# EKG_Modul_III.net
KiCad netlist of a schematic drawn in EAGLE
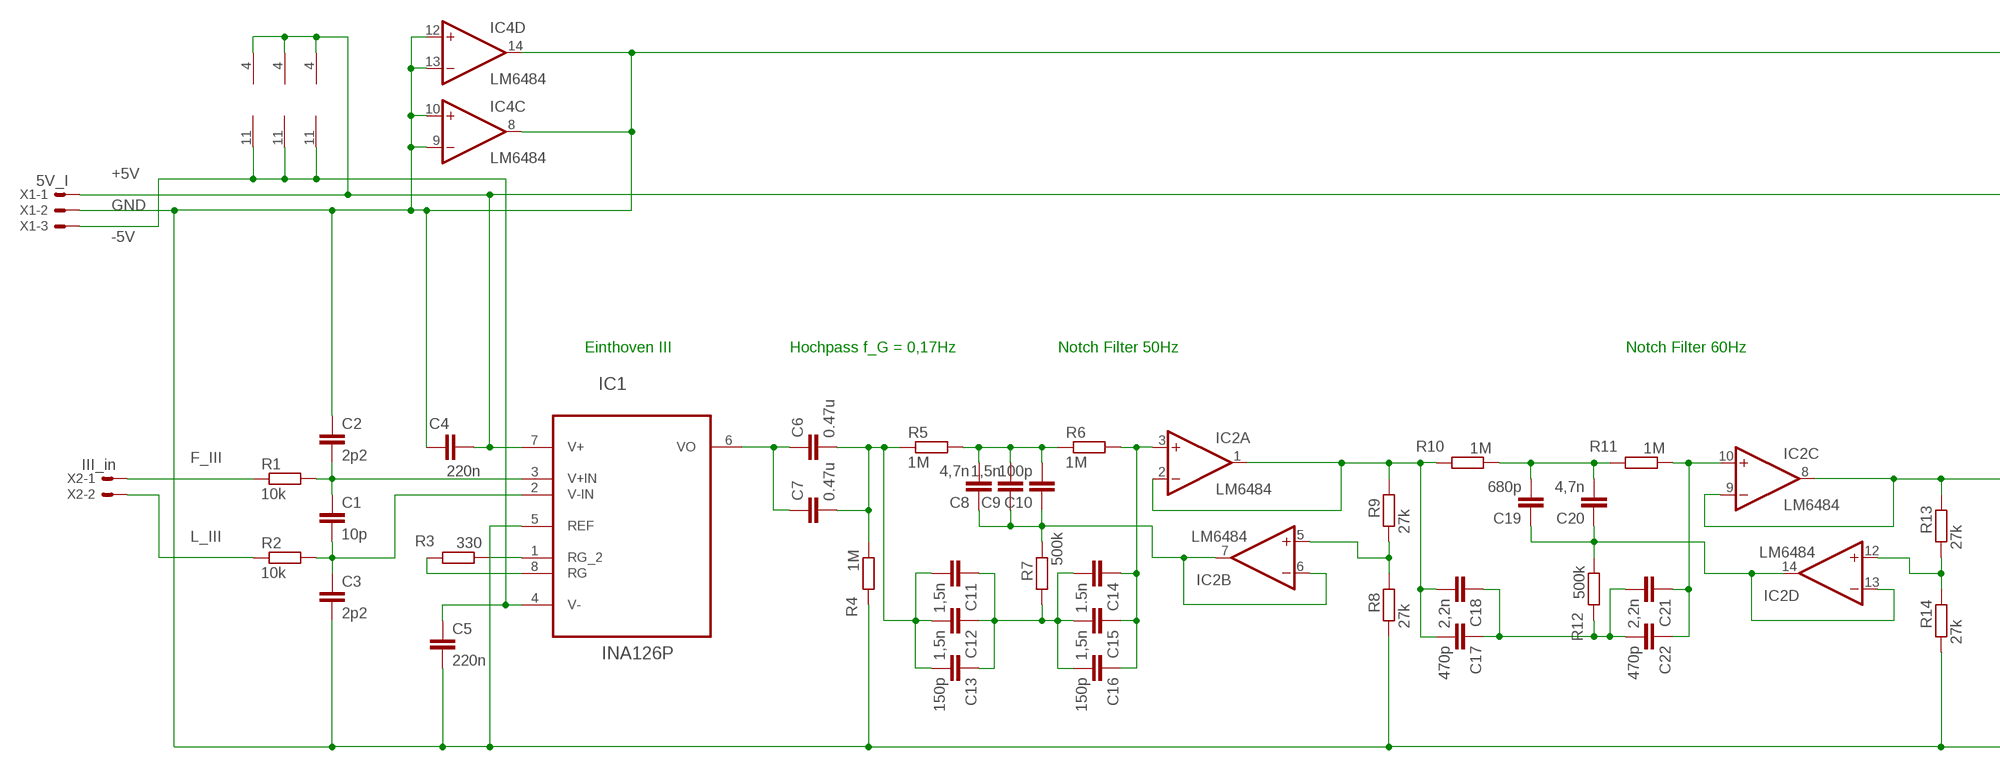
[diagram p0: schematic, sheet 1, part 1 of 2]
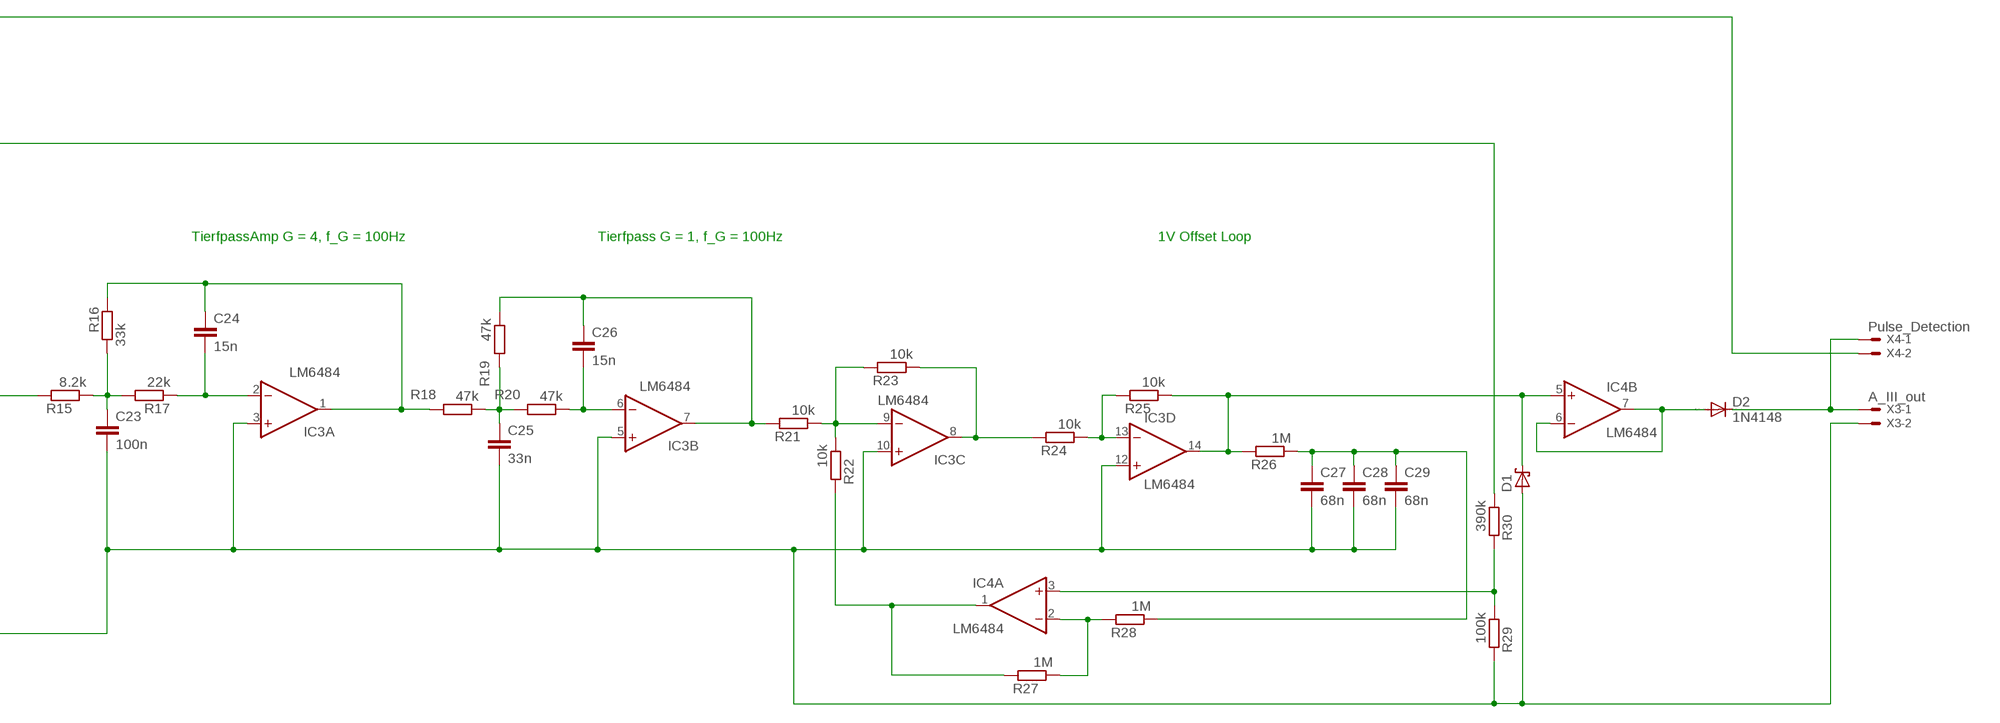
[diagram p1: schematic, sheet 1, part 2 of 2]

(export (version "E")
  (design (tool "Eeschema 10.0.6"))
  (components
    (comp (ref "C1")
      (value "10p")
      (footprint "eagle-import:C2.5-2")
      (libsource (lib "eagle-import") (part "C2.5/2"))
    )
    (comp (ref "C2")
      (value "2p2")
      (footprint "eagle-import:C2.5-2")
      (libsource (lib "eagle-import") (part "C2.5/2"))
    )
    (comp (ref "C3")
      (value "2p2")
      (footprint "eagle-import:C2.5-2")
      (libsource (lib "eagle-import") (part "C2.5/2"))
    )
    (comp (ref "C4")
      (value "220n")
      (footprint "eagle-import:C2.5-2")
      (libsource (lib "eagle-import") (part "C2.5/2"))
    )
    (comp (ref "C5")
      (value "220n")
      (footprint "eagle-import:C2.5-2")
      (libsource (lib "eagle-import") (part "C2.5/2"))
    )
    (comp (ref "C6")
      (value "0.47u")
      (footprint "eagle-import:C15B5")
      (libsource (lib "eagle-import") (part "C15/5"))
    )
    (comp (ref "C7")
      (value "0.47u")
      (footprint "eagle-import:C15B5")
      (libsource (lib "eagle-import") (part "C15/5"))
    )
    (comp (ref "C8")
      (value "4,7n")
      (footprint "eagle-import:C2.5-2")
      (libsource (lib "eagle-import") (part "C2.5/2"))
    )
    (comp (ref "C9")
      (value "1,5n")
      (footprint "eagle-import:C2.5-2")
      (libsource (lib "eagle-import") (part "C2.5/2"))
    )
    (comp (ref "C10")
      (value "100p")
      (footprint "eagle-import:C2.5-2")
      (libsource (lib "eagle-import") (part "C2.5/2"))
    )
    (comp (ref "C11")
      (value "1,5n")
      (footprint "eagle-import:C2.5-2")
      (libsource (lib "eagle-import") (part "C2.5/2"))
    )
    (comp (ref "C12")
      (value "1,5n")
      (footprint "eagle-import:C2.5-2")
      (libsource (lib "eagle-import") (part "C2.5/2"))
    )
    (comp (ref "C13")
      (value "150p")
      (footprint "eagle-import:C2.5-2")
      (libsource (lib "eagle-import") (part "C2.5/2"))
    )
    (comp (ref "C14")
      (value "1.5n")
      (footprint "eagle-import:C2.5-2")
      (libsource (lib "eagle-import") (part "C2.5/2"))
    )
    (comp (ref "C15")
      (value "1,5n")
      (footprint "eagle-import:C2.5-2")
      (libsource (lib "eagle-import") (part "C2.5/2"))
    )
    (comp (ref "C16")
      (value "150p")
      (footprint "eagle-import:C2.5-2")
      (libsource (lib "eagle-import") (part "C2.5/2"))
    )
    (comp (ref "C17")
      (value "470p")
      (footprint "eagle-import:C2.5-2")
      (libsource (lib "eagle-import") (part "C2.5/2"))
    )
    (comp (ref "C18")
      (value "2,2n")
      (footprint "eagle-import:C2.5-2")
      (libsource (lib "eagle-import") (part "C2.5/2"))
    )
    (comp (ref "C19")
      (value "680p")
      (footprint "eagle-import:C2.5-2")
      (libsource (lib "eagle-import") (part "C2.5/2"))
    )
    (comp (ref "C20")
      (value "4,7n")
      (footprint "eagle-import:C2.5-2")
      (libsource (lib "eagle-import") (part "C2.5/2"))
    )
    (comp (ref "C21")
      (value "2,2n")
      (footprint "eagle-import:C2.5-2")
      (libsource (lib "eagle-import") (part "C2.5/2"))
    )
    (comp (ref "C22")
      (value "470p")
      (footprint "eagle-import:C2.5-2")
      (libsource (lib "eagle-import") (part "C2.5/2"))
    )
    (comp (ref "C23")
      (value "100n")
      (footprint "eagle-import:C2.5-2")
      (libsource (lib "eagle-import") (part "C2.5/2"))
    )
    (comp (ref "C24")
      (value "15n")
      (footprint "eagle-import:C2.5-2")
      (libsource (lib "eagle-import") (part "C2.5/2"))
    )
    (comp (ref "C25")
      (value "33n")
      (footprint "eagle-import:C2.5-2")
      (libsource (lib "eagle-import") (part "C2.5/2"))
    )
    (comp (ref "C26")
      (value "15n")
      (footprint "eagle-import:C2.5-2")
      (libsource (lib "eagle-import") (part "C2.5/2"))
    )
    (comp (ref "C27")
      (value "68n")
      (footprint "eagle-import:C2.5-2")
      (libsource (lib "eagle-import") (part "C2.5/2"))
    )
    (comp (ref "C28")
      (value "68n")
      (footprint "eagle-import:C2.5-2")
      (libsource (lib "eagle-import") (part "C2.5/2"))
    )
    (comp (ref "C29")
      (value "68n")
      (footprint "eagle-import:C2.5-2")
      (libsource (lib "eagle-import") (part "C2.5/2"))
    )
    (comp (ref "D1")
      (value "SCHOTTKY-DIODEDO35-7")
      (footprint "eagle-import:DO35-7")
      (libsource (lib "eagle-import") (part "SCHOTTKY-DIODEDO35-7"))
    )
    (comp (ref "D2")
      (value "1N4148")
      (footprint "eagle-import:DO35-7")
      (libsource (lib "eagle-import") (part "1N4148DO35-7"))
    )
    (comp (ref "IC1")
      (value "INA126P")
      (footprint "eagle-import:DIP254P762X508-8")
      (fields (field (name "MF") "Texas Instruments"))
      (libsource (lib "eagle-import") (part "INA126P"))
    )
    (comp (ref "IC2")
      (value "LM6484")
      (footprint "eagle-import:DIL14")
      (libsource (lib "eagle-import") (part "QUAD_OPAMPP"))
    )
    (comp (ref "IC3")
      (value "LM6484")
      (footprint "eagle-import:DIL14")
      (libsource (lib "eagle-import") (part "QUAD_OPAMPP"))
    )
    (comp (ref "IC4")
      (value "LM6484")
      (footprint "eagle-import:DIL14")
      (libsource (lib "eagle-import") (part "QUAD_OPAMPP"))
    )
    (comp (ref "R1")
      (value "10k")
      (footprint "eagle-import:0207_7")
      (libsource (lib "eagle-import") (part "R-EU_0207/7"))
    )
    (comp (ref "R2")
      (value "10k")
      (footprint "eagle-import:0207_7")
      (libsource (lib "eagle-import") (part "R-EU_0207/7"))
    )
    (comp (ref "R3")
      (value "330")
      (footprint "eagle-import:0207_7")
      (libsource (lib "eagle-import") (part "R-EU_0207/7"))
    )
    (comp (ref "R4")
      (value "1M")
      (footprint "eagle-import:0207_7")
      (libsource (lib "eagle-import") (part "R-EU_0207/7"))
    )
    (comp (ref "R5")
      (value "1M")
      (footprint "eagle-import:0207_7")
      (libsource (lib "eagle-import") (part "R-EU_0207/7"))
    )
    (comp (ref "R6")
      (value "1M")
      (footprint "eagle-import:0207_7")
      (libsource (lib "eagle-import") (part "R-EU_0207/7"))
    )
    (comp (ref "R7")
      (value "500k")
      (footprint "eagle-import:0207_7")
      (libsource (lib "eagle-import") (part "R-EU_0207/7"))
    )
    (comp (ref "R8")
      (value "27k")
      (footprint "eagle-import:0207_7")
      (libsource (lib "eagle-import") (part "R-EU_0207/7"))
    )
    (comp (ref "R9")
      (value "27k")
      (footprint "eagle-import:0207_7")
      (libsource (lib "eagle-import") (part "R-EU_0207/7"))
    )
    (comp (ref "R10")
      (value "1M")
      (footprint "eagle-import:0207_7")
      (libsource (lib "eagle-import") (part "R-EU_0207/7"))
    )
    (comp (ref "R11")
      (value "1M")
      (footprint "eagle-import:0207_7")
      (libsource (lib "eagle-import") (part "R-EU_0207/7"))
    )
    (comp (ref "R12")
      (value "500k")
      (footprint "eagle-import:0207_7")
      (libsource (lib "eagle-import") (part "R-EU_0207/7"))
    )
    (comp (ref "R13")
      (value "27k")
      (footprint "eagle-import:0207_7")
      (libsource (lib "eagle-import") (part "R-EU_0207/7"))
    )
    (comp (ref "R14")
      (value "27k")
      (footprint "eagle-import:0207_7")
      (libsource (lib "eagle-import") (part "R-EU_0207/7"))
    )
    (comp (ref "R15")
      (value "8.2k")
      (footprint "eagle-import:0207_7")
      (libsource (lib "eagle-import") (part "R-EU_0207/7"))
    )
    (comp (ref "R16")
      (value "33k")
      (footprint "eagle-import:0207_7")
      (libsource (lib "eagle-import") (part "R-EU_0207/7"))
    )
    (comp (ref "R17")
      (value "22k")
      (footprint "eagle-import:0207_7")
      (libsource (lib "eagle-import") (part "R-EU_0207/7"))
    )
    (comp (ref "R18")
      (value "47k")
      (footprint "eagle-import:0207_7")
      (libsource (lib "eagle-import") (part "R-EU_0207/7"))
    )
    (comp (ref "R19")
      (value "47k")
      (footprint "eagle-import:0207_7")
      (libsource (lib "eagle-import") (part "R-EU_0207/7"))
    )
    (comp (ref "R20")
      (value "47k")
      (footprint "eagle-import:0207_7")
      (libsource (lib "eagle-import") (part "R-EU_0207/7"))
    )
    (comp (ref "R21")
      (value "10k")
      (footprint "eagle-import:0207_7")
      (libsource (lib "eagle-import") (part "R-EU_0207/7"))
    )
    (comp (ref "R22")
      (value "10k")
      (footprint "eagle-import:0207_7")
      (libsource (lib "eagle-import") (part "R-EU_0207/7"))
    )
    (comp (ref "R23")
      (value "10k")
      (footprint "eagle-import:0207_7")
      (libsource (lib "eagle-import") (part "R-EU_0207/7"))
    )
    (comp (ref "R24")
      (value "10k")
      (footprint "eagle-import:0207_7")
      (libsource (lib "eagle-import") (part "R-EU_0207/7"))
    )
    (comp (ref "R25")
      (value "10k")
      (footprint "eagle-import:0207_7")
      (libsource (lib "eagle-import") (part "R-EU_0207/7"))
    )
    (comp (ref "R26")
      (value "1M")
      (footprint "eagle-import:0207_7")
      (libsource (lib "eagle-import") (part "R-EU_0207/7"))
    )
    (comp (ref "R27")
      (value "1M")
      (footprint "eagle-import:0207_7")
      (libsource (lib "eagle-import") (part "R-EU_0207/7"))
    )
    (comp (ref "R28")
      (value "1M")
      (footprint "eagle-import:0207_7")
      (libsource (lib "eagle-import") (part "R-EU_0207/7"))
    )
    (comp (ref "R29")
      (value "100k")
      (footprint "eagle-import:0207_7")
      (libsource (lib "eagle-import") (part "R-EU_0207/7"))
    )
    (comp (ref "R30")
      (value "390k")
      (footprint "eagle-import:0207_7")
      (libsource (lib "eagle-import") (part "R-EU_0207/7"))
    )
    (comp (ref "X1")
      (value "5V_I")
      (footprint "eagle-import:JST-XH-03-PACKAGE-LONG-PAD")
      (libsource (lib "eagle-import") (part "JST-XH-03-PIN-LONG-PAD"))
    )
    (comp (ref "X2")
      (value "III_in")
      (footprint "eagle-import:JST-XH-02-PACKAGE-LONG-PAD")
      (libsource (lib "eagle-import") (part "JST-XH-02-PIN-LONG-PAD"))
    )
    (comp (ref "X3")
      (value "A_III_out")
      (footprint "eagle-import:JST-XH-02-PACKAGE-LONG-PAD")
      (libsource (lib "eagle-import") (part "JST-XH-02-PIN-LONG-PAD"))
    )
    (comp (ref "X4")
      (value "Pulse_Detection")
      (footprint "eagle-import:JST-XH-02-PACKAGE-LONG-PAD")
      (libsource (lib "eagle-import") (part "JST-XH-02-PIN-LONG-PAD"))
    )
  )
  (nets
    (net (code "1") (name "/+5V") (class "Default")
      (node (ref "C4") (pin "2") (pinfunction "2_2") (pintype "passive"))
      (node (ref "IC1") (pin "7") (pinfunction "V+_7") (pintype "power_in"))
      (node (ref "IC2") (pin "4") (pinfunction "V+_4") (pintype "power_in"))
      (node (ref "IC3") (pin "4") (pinfunction "V+_4") (pintype "power_in"))
      (node (ref "IC4") (pin "4") (pinfunction "V+_4") (pintype "power_in"))
      (node (ref "R30") (pin "1") (pinfunction "1_1") (pintype "passive"))
      (node (ref "X1") (pin "1") (pinfunction "S_1") (pintype "passive"))
    )
    (net (code "2") (name "/-5V") (class "Default")
      (node (ref "C5") (pin "1") (pinfunction "1_1") (pintype "passive"))
      (node (ref "IC1") (pin "4") (pinfunction "V-_4") (pintype "power_in"))
      (node (ref "IC2") (pin "11") (pinfunction "V-_11") (pintype "power_in"))
      (node (ref "IC3") (pin "11") (pinfunction "V-_11") (pintype "power_in"))
      (node (ref "IC4") (pin "11") (pinfunction "V-_11") (pintype "power_in"))
      (node (ref "X1") (pin "3") (pinfunction "S_3") (pintype "passive"))
    )
    (net (code "3") (name "/F_III") (class "Default")
      (node (ref "R1") (pin "1") (pinfunction "1_1") (pintype "passive"))
      (node (ref "X2") (pin "1") (pinfunction "S_1") (pintype "passive"))
    )
    (net (code "4") (name "/GND") (class "Default")
      (node (ref "C2") (pin "1") (pinfunction "1_1") (pintype "passive"))
      (node (ref "C23") (pin "2") (pinfunction "2_2") (pintype "passive"))
      (node (ref "C25") (pin "2") (pinfunction "2_2") (pintype "passive"))
      (node (ref "C27") (pin "2") (pinfunction "2_2") (pintype "passive"))
      (node (ref "C28") (pin "2") (pinfunction "2_2") (pintype "passive"))
      (node (ref "C29") (pin "2") (pinfunction "2_2") (pintype "passive"))
      (node (ref "C3") (pin "2") (pinfunction "2_2") (pintype "passive"))
      (node (ref "C4") (pin "1") (pinfunction "1_1") (pintype "passive"))
      (node (ref "C5") (pin "2") (pinfunction "2_2") (pintype "passive"))
      (node (ref "D1") (pin "A") (pinfunction "A_A") (pintype "passive"))
      (node (ref "IC1") (pin "5") (pinfunction "REF_5") (pintype "passive"))
      (node (ref "IC3") (pin "10") (pinfunction "+IN_10") (pintype "input"))
      (node (ref "IC3") (pin "12") (pinfunction "+IN_12") (pintype "input"))
      (node (ref "IC3") (pin "3") (pinfunction "+IN_3") (pintype "input"))
      (node (ref "IC3") (pin "5") (pinfunction "+IN_5") (pintype "input"))
      (node (ref "IC4") (pin "10") (pinfunction "+IN_10") (pintype "input"))
      (node (ref "IC4") (pin "12") (pinfunction "+IN_12") (pintype "input"))
      (node (ref "IC4") (pin "13") (pinfunction "-IN_13") (pintype "input"))
      (node (ref "IC4") (pin "14") (pinfunction "OUT_14") (pintype "output"))
      (node (ref "IC4") (pin "8") (pinfunction "OUT_8") (pintype "output"))
      (node (ref "IC4") (pin "9") (pinfunction "-IN_9") (pintype "input"))
      (node (ref "R14") (pin "1") (pinfunction "1_1") (pintype "passive"))
      (node (ref "R29") (pin "2") (pinfunction "2_2") (pintype "passive"))
      (node (ref "R4") (pin "2") (pinfunction "2_2") (pintype "passive"))
      (node (ref "R8") (pin "1") (pinfunction "1_1") (pintype "passive"))
      (node (ref "X1") (pin "2") (pinfunction "S_2") (pintype "passive"))
      (node (ref "X3") (pin "2") (pinfunction "S_2") (pintype "passive"))
      (node (ref "X4") (pin "2") (pinfunction "S_2") (pintype "passive"))
    )
    (net (code "5") (name "/L_III") (class "Default")
      (node (ref "R2") (pin "1") (pinfunction "1_1") (pintype "passive"))
      (node (ref "X2") (pin "2") (pinfunction "S_2") (pintype "passive"))
    )
    (net (code "6") (name "Net-(C10-Pad2)") (class "Default")
      (node (ref "C10") (pin "2") (pinfunction "2_2") (pintype "passive"))
      (node (ref "C8") (pin "2") (pinfunction "2_2") (pintype "passive"))
      (node (ref "C9") (pin "2") (pinfunction "2_2") (pintype "passive"))
      (node (ref "R5") (pin "2") (pinfunction "2_2") (pintype "passive"))
      (node (ref "R6") (pin "1") (pinfunction "1_1") (pintype "passive"))
    )
    (net (code "7") (name "Net-(C11-Pad1)") (class "Default")
      (node (ref "C11") (pin "1") (pinfunction "1_1") (pintype "passive"))
      (node (ref "C12") (pin "1") (pinfunction "1_1") (pintype "passive"))
      (node (ref "C13") (pin "1") (pinfunction "1_1") (pintype "passive"))
      (node (ref "C14") (pin "2") (pinfunction "2_2") (pintype "passive"))
      (node (ref "C15") (pin "2") (pinfunction "2_2") (pintype "passive"))
      (node (ref "C16") (pin "2") (pinfunction "2_2") (pintype "passive"))
      (node (ref "R7") (pin "1") (pinfunction "1_1") (pintype "passive"))
    )
    (net (code "8") (name "Net-(C11-Pad2)") (class "Default")
      (node (ref "C11") (pin "2") (pinfunction "2_2") (pintype "passive"))
      (node (ref "C12") (pin "2") (pinfunction "2_2") (pintype "passive"))
      (node (ref "C13") (pin "2") (pinfunction "2_2") (pintype "passive"))
      (node (ref "C6") (pin "2") (pinfunction "2_2") (pintype "passive"))
      (node (ref "C7") (pin "2") (pinfunction "2_2") (pintype "passive"))
      (node (ref "R4") (pin "1") (pinfunction "1_1") (pintype "passive"))
      (node (ref "R5") (pin "1") (pinfunction "1_1") (pintype "passive"))
    )
    (net (code "9") (name "Net-(C17-Pad1)") (class "Default")
      (node (ref "C17") (pin "1") (pinfunction "1_1") (pintype "passive"))
      (node (ref "C18") (pin "1") (pinfunction "1_1") (pintype "passive"))
      (node (ref "C21") (pin "2") (pinfunction "2_2") (pintype "passive"))
      (node (ref "C22") (pin "2") (pinfunction "2_2") (pintype "passive"))
      (node (ref "R12") (pin "2") (pinfunction "2_2") (pintype "passive"))
    )
    (net (code "10") (name "Net-(C19-Pad2)") (class "Default")
      (node (ref "C19") (pin "2") (pinfunction "2_2") (pintype "passive"))
      (node (ref "C20") (pin "2") (pinfunction "2_2") (pintype "passive"))
      (node (ref "R10") (pin "1") (pinfunction "1_1") (pintype "passive"))
      (node (ref "R11") (pin "2") (pinfunction "2_2") (pintype "passive"))
    )
    (net (code "11") (name "Net-(C23-Pad1)") (class "Default")
      (node (ref "C23") (pin "1") (pinfunction "1_1") (pintype "passive"))
      (node (ref "R15") (pin "1") (pinfunction "1_1") (pintype "passive"))
      (node (ref "R16") (pin "1") (pinfunction "1_1") (pintype "passive"))
      (node (ref "R17") (pin "2") (pinfunction "2_2") (pintype "passive"))
    )
    (net (code "12") (name "Net-(C25-Pad1)") (class "Default")
      (node (ref "C25") (pin "1") (pinfunction "1_1") (pintype "passive"))
      (node (ref "R18") (pin "1") (pinfunction "1_1") (pintype "passive"))
      (node (ref "R19") (pin "2") (pinfunction "2_2") (pintype "passive"))
      (node (ref "R20") (pin "2") (pinfunction "2_2") (pintype "passive"))
    )
    (net (code "13") (name "Net-(C27-Pad1)") (class "Default")
      (node (ref "C27") (pin "1") (pinfunction "1_1") (pintype "passive"))
      (node (ref "C28") (pin "1") (pinfunction "1_1") (pintype "passive"))
      (node (ref "C29") (pin "1") (pinfunction "1_1") (pintype "passive"))
      (node (ref "R26") (pin "1") (pinfunction "1_1") (pintype "passive"))
      (node (ref "R28") (pin "1") (pinfunction "1_1") (pintype "passive"))
    )
    (net (code "14") (name "Net-(IC1-RG)") (class "Default")
      (node (ref "IC1") (pin "8") (pinfunction "RG_8") (pintype "passive"))
      (node (ref "R3") (pin "2") (pinfunction "2_2") (pintype "passive"))
    )
    (net (code "15") (name "Net-(IC1-RG_2)") (class "Default")
      (node (ref "IC1") (pin "1") (pinfunction "RG_2_1") (pintype "passive"))
      (node (ref "R3") (pin "1") (pinfunction "1_1") (pintype "passive"))
    )
    (net (code "16") (name "Net-(IC1-V+IN)") (class "Default")
      (node (ref "C1") (pin "1") (pinfunction "1_1") (pintype "passive"))
      (node (ref "C2") (pin "2") (pinfunction "2_2") (pintype "passive"))
      (node (ref "IC1") (pin "3") (pinfunction "V+IN_3") (pintype "input"))
      (node (ref "R1") (pin "2") (pinfunction "2_2") (pintype "passive"))
    )
    (net (code "17") (name "Net-(IC1-V-IN)") (class "Default")
      (node (ref "C1") (pin "2") (pinfunction "2_2") (pintype "passive"))
      (node (ref "C3") (pin "1") (pinfunction "1_1") (pintype "passive"))
      (node (ref "IC1") (pin "2") (pinfunction "V-IN_2") (pintype "input"))
      (node (ref "R2") (pin "2") (pinfunction "2_2") (pintype "passive"))
    )
    (net (code "18") (name "Net-(IC1-VO)") (class "Default")
      (node (ref "C6") (pin "1") (pinfunction "1_1") (pintype "passive"))
      (node (ref "C7") (pin "1") (pinfunction "1_1") (pintype "passive"))
      (node (ref "IC1") (pin "6") (pinfunction "VO_6") (pintype "output"))
    )
    (net (code "19") (name "Net-(IC2A-+IN)") (class "Default")
      (node (ref "C14") (pin "1") (pinfunction "1_1") (pintype "passive"))
      (node (ref "C15") (pin "1") (pinfunction "1_1") (pintype "passive"))
      (node (ref "C16") (pin "1") (pinfunction "1_1") (pintype "passive"))
      (node (ref "IC2") (pin "3") (pinfunction "+IN_3") (pintype "input"))
      (node (ref "R6") (pin "2") (pinfunction "2_2") (pintype "passive"))
    )
    (net (code "20") (name "Net-(IC2A--IN)") (class "Default")
      (node (ref "C17") (pin "2") (pinfunction "2_2") (pintype "passive"))
      (node (ref "C18") (pin "2") (pinfunction "2_2") (pintype "passive"))
      (node (ref "IC2") (pin "1") (pinfunction "OUT_1") (pintype "output"))
      (node (ref "IC2") (pin "2") (pinfunction "-IN_2") (pintype "input"))
      (node (ref "R10") (pin "2") (pinfunction "2_2") (pintype "passive"))
      (node (ref "R9") (pin "2") (pinfunction "2_2") (pintype "passive"))
    )
    (net (code "21") (name "Net-(IC2B-+IN)") (class "Default")
      (node (ref "IC2") (pin "5") (pinfunction "+IN_5") (pintype "input"))
      (node (ref "R8") (pin "2") (pinfunction "2_2") (pintype "passive"))
      (node (ref "R9") (pin "1") (pinfunction "1_1") (pintype "passive"))
    )
    (net (code "22") (name "Net-(IC2B--IN)") (class "Default")
      (node (ref "C10") (pin "1") (pinfunction "1_1") (pintype "passive"))
      (node (ref "C8") (pin "1") (pinfunction "1_1") (pintype "passive"))
      (node (ref "C9") (pin "1") (pinfunction "1_1") (pintype "passive"))
      (node (ref "IC2") (pin "6") (pinfunction "-IN_6") (pintype "input"))
      (node (ref "IC2") (pin "7") (pinfunction "OUT_7") (pintype "output"))
      (node (ref "R7") (pin "2") (pinfunction "2_2") (pintype "passive"))
    )
    (net (code "23") (name "Net-(IC2C-+IN)") (class "Default")
      (node (ref "C21") (pin "1") (pinfunction "1_1") (pintype "passive"))
      (node (ref "C22") (pin "1") (pinfunction "1_1") (pintype "passive"))
      (node (ref "IC2") (pin "10") (pinfunction "+IN_10") (pintype "input"))
      (node (ref "R11") (pin "1") (pinfunction "1_1") (pintype "passive"))
    )
    (net (code "24") (name "Net-(IC2C--IN)") (class "Default")
      (node (ref "IC2") (pin "8") (pinfunction "OUT_8") (pintype "output"))
      (node (ref "IC2") (pin "9") (pinfunction "-IN_9") (pintype "input"))
      (node (ref "R13") (pin "2") (pinfunction "2_2") (pintype "passive"))
      (node (ref "R15") (pin "2") (pinfunction "2_2") (pintype "passive"))
    )
    (net (code "25") (name "Net-(IC2D-+IN)") (class "Default")
      (node (ref "IC2") (pin "12") (pinfunction "+IN_12") (pintype "input"))
      (node (ref "R13") (pin "1") (pinfunction "1_1") (pintype "passive"))
      (node (ref "R14") (pin "2") (pinfunction "2_2") (pintype "passive"))
    )
    (net (code "26") (name "Net-(IC2D--IN)") (class "Default")
      (node (ref "C19") (pin "1") (pinfunction "1_1") (pintype "passive"))
      (node (ref "C20") (pin "1") (pinfunction "1_1") (pintype "passive"))
      (node (ref "IC2") (pin "13") (pinfunction "-IN_13") (pintype "input"))
      (node (ref "IC2") (pin "14") (pinfunction "OUT_14") (pintype "output"))
      (node (ref "R12") (pin "1") (pinfunction "1_1") (pintype "passive"))
    )
    (net (code "27") (name "Net-(IC3A--IN)") (class "Default")
      (node (ref "C24") (pin "2") (pinfunction "2_2") (pintype "passive"))
      (node (ref "IC3") (pin "2") (pinfunction "-IN_2") (pintype "input"))
      (node (ref "R17") (pin "1") (pinfunction "1_1") (pintype "passive"))
    )
    (net (code "28") (name "Net-(IC3A-OUT)") (class "Default")
      (node (ref "C24") (pin "1") (pinfunction "1_1") (pintype "passive"))
      (node (ref "IC3") (pin "1") (pinfunction "OUT_1") (pintype "output"))
      (node (ref "R16") (pin "2") (pinfunction "2_2") (pintype "passive"))
      (node (ref "R18") (pin "2") (pinfunction "2_2") (pintype "passive"))
    )
    (net (code "29") (name "Net-(IC3B--IN)") (class "Default")
      (node (ref "C26") (pin "2") (pinfunction "2_2") (pintype "passive"))
      (node (ref "IC3") (pin "6") (pinfunction "-IN_6") (pintype "input"))
      (node (ref "R20") (pin "1") (pinfunction "1_1") (pintype "passive"))
    )
    (net (code "30") (name "Net-(IC3B-OUT)") (class "Default")
      (node (ref "C26") (pin "1") (pinfunction "1_1") (pintype "passive"))
      (node (ref "IC3") (pin "7") (pinfunction "OUT_7") (pintype "output"))
      (node (ref "R19") (pin "1") (pinfunction "1_1") (pintype "passive"))
      (node (ref "R21") (pin "2") (pinfunction "2_2") (pintype "passive"))
    )
    (net (code "31") (name "Net-(IC3C--IN)") (class "Default")
      (node (ref "IC3") (pin "9") (pinfunction "-IN_9") (pintype "input"))
      (node (ref "R21") (pin "1") (pinfunction "1_1") (pintype "passive"))
      (node (ref "R22") (pin "1") (pinfunction "1_1") (pintype "passive"))
      (node (ref "R23") (pin "2") (pinfunction "2_2") (pintype "passive"))
    )
    (net (code "32") (name "Net-(IC3C-OUT)") (class "Default")
      (node (ref "IC3") (pin "8") (pinfunction "OUT_8") (pintype "output"))
      (node (ref "R23") (pin "1") (pinfunction "1_1") (pintype "passive"))
      (node (ref "R24") (pin "2") (pinfunction "2_2") (pintype "passive"))
    )
    (net (code "33") (name "Net-(IC3D--IN)") (class "Default")
      (node (ref "IC3") (pin "13") (pinfunction "-IN_13") (pintype "input"))
      (node (ref "R24") (pin "1") (pinfunction "1_1") (pintype "passive"))
      (node (ref "R25") (pin "2") (pinfunction "2_2") (pintype "passive"))
    )
    (net (code "34") (name "Net-(IC3D-OUT)") (class "Default")
      (node (ref "D1") (pin "C") (pinfunction "C_C") (pintype "passive"))
      (node (ref "IC3") (pin "14") (pinfunction "OUT_14") (pintype "output"))
      (node (ref "IC4") (pin "5") (pinfunction "+IN_5") (pintype "input"))
      (node (ref "R25") (pin "1") (pinfunction "1_1") (pintype "passive"))
      (node (ref "R26") (pin "2") (pinfunction "2_2") (pintype "passive"))
    )
    (net (code "35") (name "Net-(IC4A-+IN)") (class "Default")
      (node (ref "IC4") (pin "3") (pinfunction "+IN_3") (pintype "input"))
      (node (ref "R29") (pin "1") (pinfunction "1_1") (pintype "passive"))
      (node (ref "R30") (pin "2") (pinfunction "2_2") (pintype "passive"))
    )
    (net (code "36") (name "Net-(IC4A--IN)") (class "Default")
      (node (ref "IC4") (pin "2") (pinfunction "-IN_2") (pintype "input"))
      (node (ref "R27") (pin "1") (pinfunction "1_1") (pintype "passive"))
      (node (ref "R28") (pin "2") (pinfunction "2_2") (pintype "passive"))
    )
    (net (code "37") (name "Net-(IC4A-OUT)") (class "Default")
      (node (ref "IC4") (pin "1") (pinfunction "OUT_1") (pintype "output"))
      (node (ref "R22") (pin "2") (pinfunction "2_2") (pintype "passive"))
      (node (ref "R27") (pin "2") (pinfunction "2_2") (pintype "passive"))
    )
    (net (code "38") (name "Net-(IC4B--IN)") (class "Default")
      (node (ref "D2") (pin "A") (pinfunction "A_A") (pintype "passive"))
      (node (ref "IC4") (pin "6") (pinfunction "-IN_6") (pintype "input"))
      (node (ref "IC4") (pin "7") (pinfunction "OUT_7") (pintype "output"))
    )
    (net (code "39") (name "Net-(X3A-S)") (class "Default")
      (node (ref "D2") (pin "C") (pinfunction "C_C") (pintype "passive"))
      (node (ref "X3") (pin "1") (pinfunction "S_1") (pintype "passive"))
      (node (ref "X4") (pin "1") (pinfunction "S_1") (pintype "passive"))
    )
  )
)
